# USB-C-touch.net
KiCad netlist of a schematic drawn in EAGLE
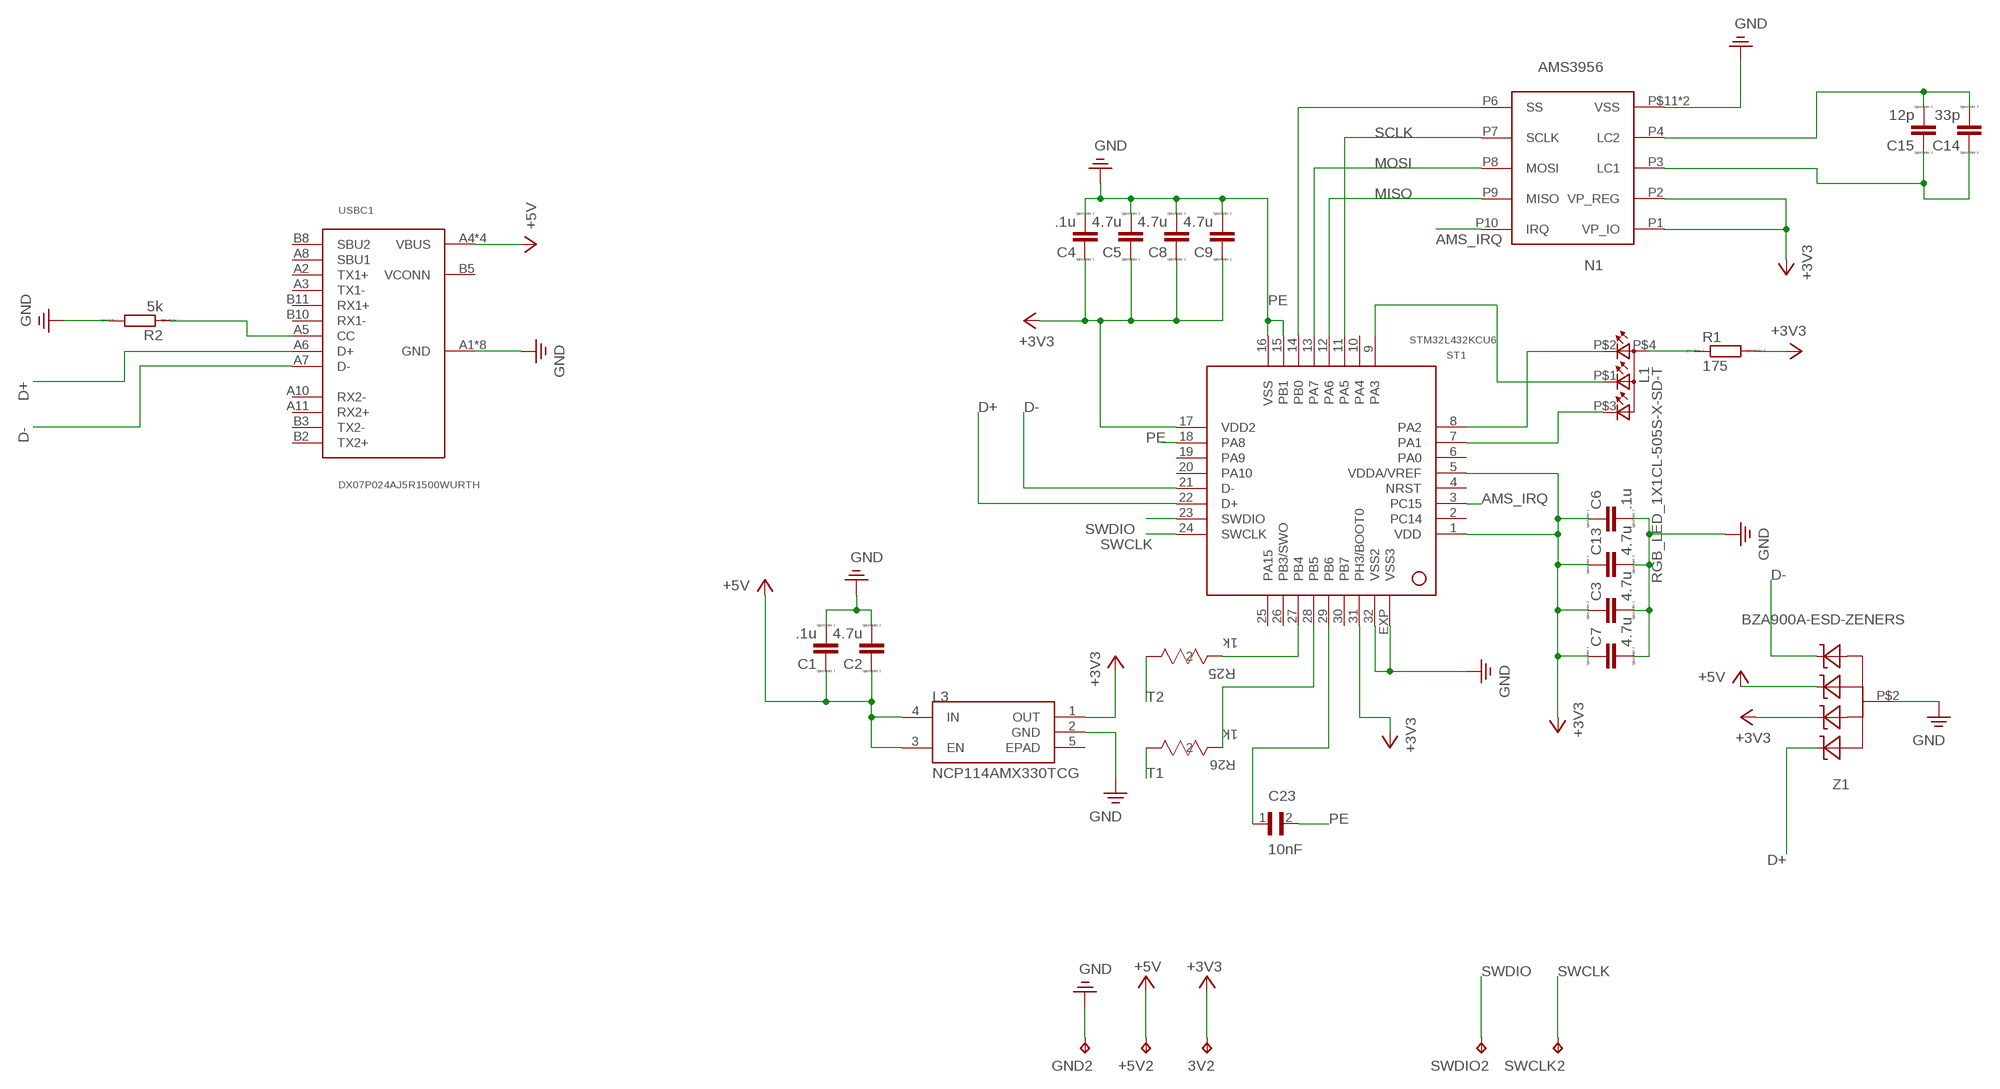
[diagram p0: schematic, sheet 1]

(export (version "E")
  (design (tool "Eeschema 10.0.6"))
  (components
    (comp (ref "+5V2")
      (value "TEST_POINT")
      (footprint "eagle-import:B1,27")
      (libsource (lib "eagle-import") (part "TEST_POINT"))
    )
    (comp (ref "3V2")
      (value "TEST_POINT")
      (footprint "eagle-import:B1,27")
      (libsource (lib "eagle-import") (part "TEST_POINT"))
    )
    (comp (ref "C1")
      (value ".1u")
      (footprint "eagle-import:C0402")
      (libsource (lib "eagle-import") (part "CAPACITOR"))
    )
    (comp (ref "C2")
      (value "4.7u")
      (footprint "eagle-import:C0402")
      (libsource (lib "eagle-import") (part "CAPACITOR"))
    )
    (comp (ref "C3")
      (value "4.7u")
      (footprint "eagle-import:C0402")
      (libsource (lib "eagle-import") (part "CAPACITOR"))
    )
    (comp (ref "C4")
      (value ".1u")
      (footprint "eagle-import:C0402")
      (libsource (lib "eagle-import") (part "CAPACITOR"))
    )
    (comp (ref "C5")
      (value "4.7u")
      (footprint "eagle-import:C0402")
      (libsource (lib "eagle-import") (part "CAPACITOR"))
    )
    (comp (ref "C6")
      (value ".1u")
      (footprint "eagle-import:C0402")
      (libsource (lib "eagle-import") (part "CAPACITOR"))
    )
    (comp (ref "C7")
      (value "4.7u")
      (footprint "eagle-import:C0402")
      (libsource (lib "eagle-import") (part "CAPACITOR"))
    )
    (comp (ref "C8")
      (value "4.7u")
      (footprint "eagle-import:C0402")
      (libsource (lib "eagle-import") (part "CAPACITOR"))
    )
    (comp (ref "C9")
      (value "4.7u")
      (footprint "eagle-import:C0402")
      (libsource (lib "eagle-import") (part "CAPACITOR"))
    )
    (comp (ref "C13")
      (value "4.7u")
      (footprint "eagle-import:C0402")
      (libsource (lib "eagle-import") (part "CAPACITOR"))
    )
    (comp (ref "C14")
      (value "33p")
      (footprint "eagle-import:C0402")
      (libsource (lib "eagle-import") (part "CAPACITOR"))
    )
    (comp (ref "C15")
      (value "12p")
      (footprint "eagle-import:C0402")
      (libsource (lib "eagle-import") (part "CAPACITOR"))
    )
    (comp (ref "C23")
      (value "10nF")
      (footprint "eagle-import:CAPC2012X95N")
      (fields
        (field (name "DIGI-KEY_PART_NUMBER") "490-8295-1-ND")
        (field (name "MF") "Murata")
        (field (name "MP") "GRM2195C1H103FA01D")
      )
      (libsource (lib "eagle-import") (part "GRM2195C1H103FA01D"))
    )
    (comp (ref "GND2")
      (value "TEST_POINT")
      (footprint "eagle-import:B1,27")
      (libsource (lib "eagle-import") (part "TEST_POINT"))
    )
    (comp (ref "L1")
      (value "RGB_LED_1X1CL-505S-X-SD-T")
      (footprint "eagle-import:CL-505S-X-SD-T")
      (libsource (lib "eagle-import") (part "RGB_LED_1X1CL-505S-X-SD-T"))
    )
    (comp (ref "L3")
      (value "NCP114AMX330TCG")
      (footprint "eagle-import:REG_NCP114AMX330TCG")
      (fields (field (name "MF") "ON Semiconductor"))
      (libsource (lib "eagle-import") (part "NCP114AMX330TCG"))
    )
    (comp (ref "N1")
      (value "AMS3956")
      (footprint "eagle-import:MLPD3X3")
      (libsource (lib "eagle-import") (part "AMS3956"))
    )
    (comp (ref "R1")
      (value "175")
      (footprint "eagle-import:R0402")
      (libsource (lib "eagle-import") (part "RESISTOR"))
    )
    (comp (ref "R2")
      (value "5k")
      (footprint "eagle-import:R0402")
      (libsource (lib "eagle-import") (part "RESISTOR"))
    )
    (comp (ref "R25")
      (value "1k")
      (footprint "eagle-import:RC0402N-L")
      (fields (field (name "MANUFACTURER_PART_NUMBER") "RC0402FR071KL"))
      (libsource (lib "eagle-import") (part "RC0402FR-071KLRC0402N-L"))
    )
    (comp (ref "R26")
      (value "1k")
      (footprint "eagle-import:RC0402N-L")
      (fields (field (name "MANUFACTURER_PART_NUMBER") "RC0402FR071KL"))
      (libsource (lib "eagle-import") (part "RC0402FR-071KLRC0402N-L"))
    )
    (comp (ref "ST1")
      (value "STM32L432KCU6")
      (footprint "eagle-import:QFN32")
      (libsource (lib "eagle-import") (part "STM32L432KCU6"))
    )
    (comp (ref "SWCLK2")
      (value "TEST_POINT")
      (footprint "eagle-import:B1,27")
      (libsource (lib "eagle-import") (part "TEST_POINT"))
    )
    (comp (ref "SWDIO2")
      (value "TEST_POINT")
      (footprint "eagle-import:B1,27")
      (libsource (lib "eagle-import") (part "TEST_POINT"))
    )
    (comp (ref "USBC1")
      (value "DX07P024AJ5R1500WURTH")
      (footprint "eagle-import:WüRTH_632712000112")
      (libsource (lib "eagle-import") (part "DX07P024AJ5R1500WURTH"))
    )
    (comp (ref "Z1")
      (value "BZA900A-ESD-ZENERS")
      (footprint "eagle-import:BZA900A")
      (libsource (lib "eagle-import") (part "BZA900A-ESD-ZENERS"))
    )
  )
  (nets
    (net (code "1") (name "+3V3") (class "Default")
      (node (ref "3V2") (pin "TP") (pinfunction "TP_TP") (pintype "input"))
      (node (ref "C13") (pin "1") (pinfunction "1_1") (pintype "passive"))
      (node (ref "C3") (pin "1") (pinfunction "1_1") (pintype "passive"))
      (node (ref "C4") (pin "1") (pinfunction "1_1") (pintype "passive"))
      (node (ref "C5") (pin "1") (pinfunction "1_1") (pintype "passive"))
      (node (ref "C6") (pin "1") (pinfunction "1_1") (pintype "passive"))
      (node (ref "C7") (pin "1") (pinfunction "1_1") (pintype "passive"))
      (node (ref "C8") (pin "1") (pinfunction "1_1") (pintype "passive"))
      (node (ref "C9") (pin "1") (pinfunction "1_1") (pintype "passive"))
      (node (ref "L3") (pin "1") (pinfunction "OUT_1") (pintype "output"))
      (node (ref "N1") (pin "P1") (pinfunction "VP_IO_P1") (pintype "bidirectional"))
      (node (ref "N1") (pin "P2") (pinfunction "VP_REG_P2") (pintype "bidirectional"))
      (node (ref "R1") (pin "2") (pinfunction "2_2") (pintype "passive"))
      (node (ref "ST1") (pin "1") (pinfunction "VDD_1") (pintype "bidirectional"))
      (node (ref "ST1") (pin "17") (pinfunction "VDD2_17") (pintype "bidirectional"))
      (node (ref "ST1") (pin "31") (pinfunction "PH3/BOOT0_31") (pintype "bidirectional"))
      (node (ref "ST1") (pin "5") (pinfunction "VDDA/VREF_5") (pintype "bidirectional"))
      (node (ref "Z1") (pin "P$5") (pinfunction "C1_P$5") (pintype "passive"))
    )
    (net (code "2") (name "+5V") (class "Default")
      (node (ref "+5V2") (pin "TP") (pinfunction "TP_TP") (pintype "input"))
      (node (ref "C1") (pin "1") (pinfunction "1_1") (pintype "passive"))
      (node (ref "C2") (pin "1") (pinfunction "1_1") (pintype "passive"))
      (node (ref "L3") (pin "3") (pinfunction "EN_3") (pintype "input"))
      (node (ref "L3") (pin "4") (pinfunction "IN_4") (pintype "input"))
      (node (ref "USBC1") (pin "A4") (pinfunction "VBUS_A4") (pintype "bidirectional"))
      (node (ref "USBC1") (pin "A9") (pinfunction "VBUS_A9") (pintype "bidirectional"))
      (node (ref "USBC1") (pin "B4") (pinfunction "VBUS_B4") (pintype "bidirectional"))
      (node (ref "USBC1") (pin "B9") (pinfunction "VBUS_B9") (pintype "bidirectional"))
      (node (ref "Z1") (pin "P$1") (pinfunction "C_P$1") (pintype "passive"))
    )
    (net (code "3") (name "/AMS_IRQ") (class "Default")
      (node (ref "N1") (pin "P10") (pinfunction "IRQ_P10") (pintype "bidirectional"))
      (node (ref "ST1") (pin "3") (pinfunction "PC15_3") (pintype "bidirectional"))
    )
    (net (code "4") (name "/D+") (class "Default")
      (node (ref "ST1") (pin "22") (pinfunction "D+_22") (pintype "bidirectional"))
      (node (ref "USBC1") (pin "A6") (pinfunction "D+_A6") (pintype "bidirectional"))
      (node (ref "Z1") (pin "P$3") (pinfunction "C3_P$3") (pintype "passive"))
    )
    (net (code "5") (name "/D-") (class "Default")
      (node (ref "ST1") (pin "21") (pinfunction "D-_21") (pintype "bidirectional"))
      (node (ref "USBC1") (pin "A7") (pinfunction "D-_A7") (pintype "bidirectional"))
      (node (ref "Z1") (pin "P$4") (pinfunction "C2_P$4") (pintype "passive"))
    )
    (net (code "6") (name "/MISO") (class "Default")
      (node (ref "N1") (pin "P9") (pinfunction "MISO_P9") (pintype "bidirectional"))
      (node (ref "ST1") (pin "12") (pinfunction "PA6_12") (pintype "bidirectional"))
    )
    (net (code "7") (name "/MOSI") (class "Default")
      (node (ref "N1") (pin "P8") (pinfunction "MOSI_P8") (pintype "bidirectional"))
      (node (ref "ST1") (pin "13") (pinfunction "PA7_13") (pintype "bidirectional"))
    )
    (net (code "8") (name "/SCLK") (class "Default")
      (node (ref "N1") (pin "P7") (pinfunction "SCLK_P7") (pintype "bidirectional"))
      (node (ref "ST1") (pin "11") (pinfunction "PA5_11") (pintype "bidirectional"))
    )
    (net (code "9") (name "/SWCLK") (class "Default")
      (node (ref "ST1") (pin "24") (pinfunction "SWCLK_24") (pintype "bidirectional"))
      (node (ref "SWCLK2") (pin "TP") (pinfunction "TP_TP") (pintype "input"))
    )
    (net (code "10") (name "/SWDIO") (class "Default")
      (node (ref "ST1") (pin "23") (pinfunction "SWDIO_23") (pintype "bidirectional"))
      (node (ref "SWDIO2") (pin "TP") (pinfunction "TP_TP") (pintype "input"))
    )
    (net (code "11") (name "/T1") (class "Default")
      (node (ref "R26") (pin "1") (pinfunction "1_1") (pintype "passive"))
    )
    (net (code "12") (name "/T2") (class "Default")
      (node (ref "R25") (pin "1") (pinfunction "1_1") (pintype "passive"))
    )
    (net (code "13") (name "GND") (class "Default")
      (node (ref "C1") (pin "2") (pinfunction "2_2") (pintype "passive"))
      (node (ref "C13") (pin "2") (pinfunction "2_2") (pintype "passive"))
      (node (ref "C2") (pin "2") (pinfunction "2_2") (pintype "passive"))
      (node (ref "C23") (pin "2") (pinfunction "2_2") (pintype "passive"))
      (node (ref "C3") (pin "2") (pinfunction "2_2") (pintype "passive"))
      (node (ref "C4") (pin "2") (pinfunction "2_2") (pintype "passive"))
      (node (ref "C5") (pin "2") (pinfunction "2_2") (pintype "passive"))
      (node (ref "C6") (pin "2") (pinfunction "2_2") (pintype "passive"))
      (node (ref "C7") (pin "2") (pinfunction "2_2") (pintype "passive"))
      (node (ref "C8") (pin "2") (pinfunction "2_2") (pintype "passive"))
      (node (ref "C9") (pin "2") (pinfunction "2_2") (pintype "passive"))
      (node (ref "GND2") (pin "TP") (pinfunction "TP_TP") (pintype "input"))
      (node (ref "L3") (pin "2") (pinfunction "GND_2") (pintype "power_in"))
      (node (ref "N1") (pin "P$11") (pinfunction "VSS_P$11") (pintype "bidirectional"))
      (node (ref "N1") (pin "P5") (pinfunction "VSS_P5") (pintype "bidirectional"))
      (node (ref "R2") (pin "2") (pinfunction "2_2") (pintype "passive"))
      (node (ref "ST1") (pin "15") (pinfunction "PB1_15") (pintype "bidirectional"))
      (node (ref "ST1") (pin "16") (pinfunction "VSS_16") (pintype "bidirectional"))
      (node (ref "ST1") (pin "18") (pinfunction "PA8_18") (pintype "bidirectional"))
      (node (ref "ST1") (pin "32") (pinfunction "VSS2_32") (pintype "bidirectional"))
      (node (ref "ST1") (pin "EXP") (pinfunction "VSS3_EXP") (pintype "bidirectional"))
      (node (ref "USBC1") (pin "A1") (pinfunction "GND_A1") (pintype "bidirectional"))
      (node (ref "USBC1") (pin "A12") (pinfunction "GND_A12") (pintype "bidirectional"))
      (node (ref "USBC1") (pin "B1") (pinfunction "GND_B1") (pintype "bidirectional"))
      (node (ref "USBC1") (pin "B12") (pinfunction "GND_B12") (pintype "bidirectional"))
      (node (ref "USBC1") (pin "P_GND1") (pinfunction "GND_P_GND1") (pintype "bidirectional"))
      (node (ref "USBC1") (pin "P_GND2") (pinfunction "GND_P_GND2") (pintype "bidirectional"))
      (node (ref "USBC1") (pin "P_GND3") (pinfunction "GND_P_GND3") (pintype "bidirectional"))
      (node (ref "USBC1") (pin "P_GND4") (pinfunction "GND_P_GND4") (pintype "bidirectional"))
      (node (ref "Z1") (pin "P$2") (pinfunction "P$1_P$2") (pintype "bidirectional"))
    )
    (net (code "14") (name "Net-(L1-A2)") (class "Default")
      (node (ref "L1") (pin "P$4") (pinfunction "A2_P$4") (pintype "passive"))
      (node (ref "R1") (pin "1") (pinfunction "1_1") (pintype "passive"))
    )
    (net (code "15") (name "Net-(L1-CBLUE)") (class "Default")
      (node (ref "L1") (pin "P$1") (pinfunction "CBLUE_P$1") (pintype "passive"))
      (node (ref "ST1") (pin "9") (pinfunction "PA3_9") (pintype "bidirectional"))
    )
    (net (code "16") (name "Net-(L1-CGREEN)") (class "Default")
      (node (ref "L1") (pin "P$3") (pinfunction "CGREEN_P$3") (pintype "passive"))
      (node (ref "ST1") (pin "7") (pinfunction "PA1_7") (pintype "bidirectional"))
    )
    (net (code "17") (name "Net-(L1-CRED)") (class "Default")
      (node (ref "L1") (pin "P$2") (pinfunction "CRED_P$2") (pintype "passive"))
      (node (ref "ST1") (pin "8") (pinfunction "PA2_8") (pintype "bidirectional"))
    )
    (net (code "18") (name "Net-(N1-LC1)") (class "Default")
      (node (ref "C14") (pin "1") (pinfunction "1_1") (pintype "passive"))
      (node (ref "C15") (pin "1") (pinfunction "1_1") (pintype "passive"))
      (node (ref "N1") (pin "P3") (pinfunction "LC1_P3") (pintype "bidirectional"))
    )
    (net (code "19") (name "Net-(N1-LC2)") (class "Default")
      (node (ref "C14") (pin "2") (pinfunction "2_2") (pintype "passive"))
      (node (ref "C15") (pin "2") (pinfunction "2_2") (pintype "passive"))
      (node (ref "N1") (pin "P4") (pinfunction "LC2_P4") (pintype "bidirectional"))
    )
    (net (code "20") (name "Net-(N1-SS)") (class "Default")
      (node (ref "N1") (pin "P6") (pinfunction "SS_P6") (pintype "bidirectional"))
      (node (ref "ST1") (pin "14") (pinfunction "PB0_14") (pintype "bidirectional"))
    )
    (net (code "21") (name "Net-(ST1-PB4)") (class "Default")
      (node (ref "R25") (pin "2") (pinfunction "2_2") (pintype "passive"))
      (node (ref "ST1") (pin "27") (pinfunction "PB4_27") (pintype "bidirectional"))
    )
    (net (code "22") (name "Net-(ST1-PB5)") (class "Default")
      (node (ref "R26") (pin "2") (pinfunction "2_2") (pintype "passive"))
      (node (ref "ST1") (pin "28") (pinfunction "PB5_28") (pintype "bidirectional"))
    )
    (net (code "23") (name "Net-(ST1-PB6)") (class "Default")
      (node (ref "C23") (pin "1") (pinfunction "1_1") (pintype "passive"))
      (node (ref "ST1") (pin "29") (pinfunction "PB6_29") (pintype "bidirectional"))
    )
    (net (code "24") (name "Net-(USBC1-CC)") (class "Default")
      (node (ref "R2") (pin "1") (pinfunction "1_1") (pintype "passive"))
      (node (ref "USBC1") (pin "A5") (pinfunction "CC_A5") (pintype "bidirectional"))
    )
    (net (code "25") (name "unconnected-(L3-EPAD-Pad5)") (class "Default")
      (node (ref "L3") (pin "5") (pinfunction "EPAD_5") (pintype "passive"))
    )
    (net (code "26") (name "unconnected-(ST1-NRST-Pad4)") (class "Default")
      (node (ref "ST1") (pin "4") (pinfunction "NRST_4") (pintype "bidirectional"))
    )
    (net (code "27") (name "unconnected-(ST1-PA0-Pad6)") (class "Default")
      (node (ref "ST1") (pin "6") (pinfunction "PA0_6") (pintype "bidirectional"))
    )
    (net (code "28") (name "unconnected-(ST1-PA4-Pad10)") (class "Default")
      (node (ref "ST1") (pin "10") (pinfunction "PA4_10") (pintype "bidirectional"))
    )
    (net (code "29") (name "unconnected-(ST1-PA9-Pad19)") (class "Default")
      (node (ref "ST1") (pin "19") (pinfunction "PA9_19") (pintype "bidirectional"))
    )
    (net (code "30") (name "unconnected-(ST1-PA10-Pad20)") (class "Default")
      (node (ref "ST1") (pin "20") (pinfunction "PA10_20") (pintype "bidirectional"))
    )
    (net (code "31") (name "unconnected-(ST1-PA15-Pad25)") (class "Default")
      (node (ref "ST1") (pin "25") (pinfunction "PA15_25") (pintype "bidirectional"))
    )
    (net (code "32") (name "unconnected-(ST1-PB3{slash}SWO-Pad26)") (class "Default")
      (node (ref "ST1") (pin "26") (pinfunction "PB3/SWO_26") (pintype "bidirectional"))
    )
    (net (code "33") (name "unconnected-(ST1-PB7-Pad30)") (class "Default")
      (node (ref "ST1") (pin "30") (pinfunction "PB7_30") (pintype "bidirectional"))
    )
    (net (code "34") (name "unconnected-(ST1-PC14-Pad2)") (class "Default")
      (node (ref "ST1") (pin "2") (pinfunction "PC14_2") (pintype "bidirectional"))
    )
    (net (code "35") (name "unconnected-(USBC1-RX1+-PadB11)") (class "Default")
      (node (ref "USBC1") (pin "B11") (pinfunction "RX1+_B11") (pintype "bidirectional"))
    )
    (net (code "36") (name "unconnected-(USBC1-RX1--PadB10)") (class "Default")
      (node (ref "USBC1") (pin "B10") (pinfunction "RX1-_B10") (pintype "bidirectional"))
    )
    (net (code "37") (name "unconnected-(USBC1-RX2+-PadA11)") (class "Default")
      (node (ref "USBC1") (pin "A11") (pinfunction "RX2+_A11") (pintype "bidirectional"))
    )
    (net (code "38") (name "unconnected-(USBC1-RX2--PadA10)") (class "Default")
      (node (ref "USBC1") (pin "A10") (pinfunction "RX2-_A10") (pintype "bidirectional"))
    )
    (net (code "39") (name "unconnected-(USBC1-SBU1-PadA8)") (class "Default")
      (node (ref "USBC1") (pin "A8") (pinfunction "SBU1_A8") (pintype "bidirectional"))
    )
    (net (code "40") (name "unconnected-(USBC1-SBU2-PadB8)") (class "Default")
      (node (ref "USBC1") (pin "B8") (pinfunction "SBU2_B8") (pintype "bidirectional"))
    )
    (net (code "41") (name "unconnected-(USBC1-TX1+-PadA2)") (class "Default")
      (node (ref "USBC1") (pin "A2") (pinfunction "TX1+_A2") (pintype "bidirectional"))
    )
    (net (code "42") (name "unconnected-(USBC1-TX1--PadA3)") (class "Default")
      (node (ref "USBC1") (pin "A3") (pinfunction "TX1-_A3") (pintype "bidirectional"))
    )
    (net (code "43") (name "unconnected-(USBC1-TX2+-PadB2)") (class "Default")
      (node (ref "USBC1") (pin "B2") (pinfunction "TX2+_B2") (pintype "bidirectional"))
    )
    (net (code "44") (name "unconnected-(USBC1-TX2--PadB3)") (class "Default")
      (node (ref "USBC1") (pin "B3") (pinfunction "TX2-_B3") (pintype "bidirectional"))
    )
    (net (code "45") (name "unconnected-(USBC1-VCONN-PadB5)") (class "Default")
      (node (ref "USBC1") (pin "B5") (pinfunction "VCONN_B5") (pintype "bidirectional"))
    )
  )
)
